# 0009_e_field_probe_5mm.net
KiCad netlist of a schematic drawn in EAGLE
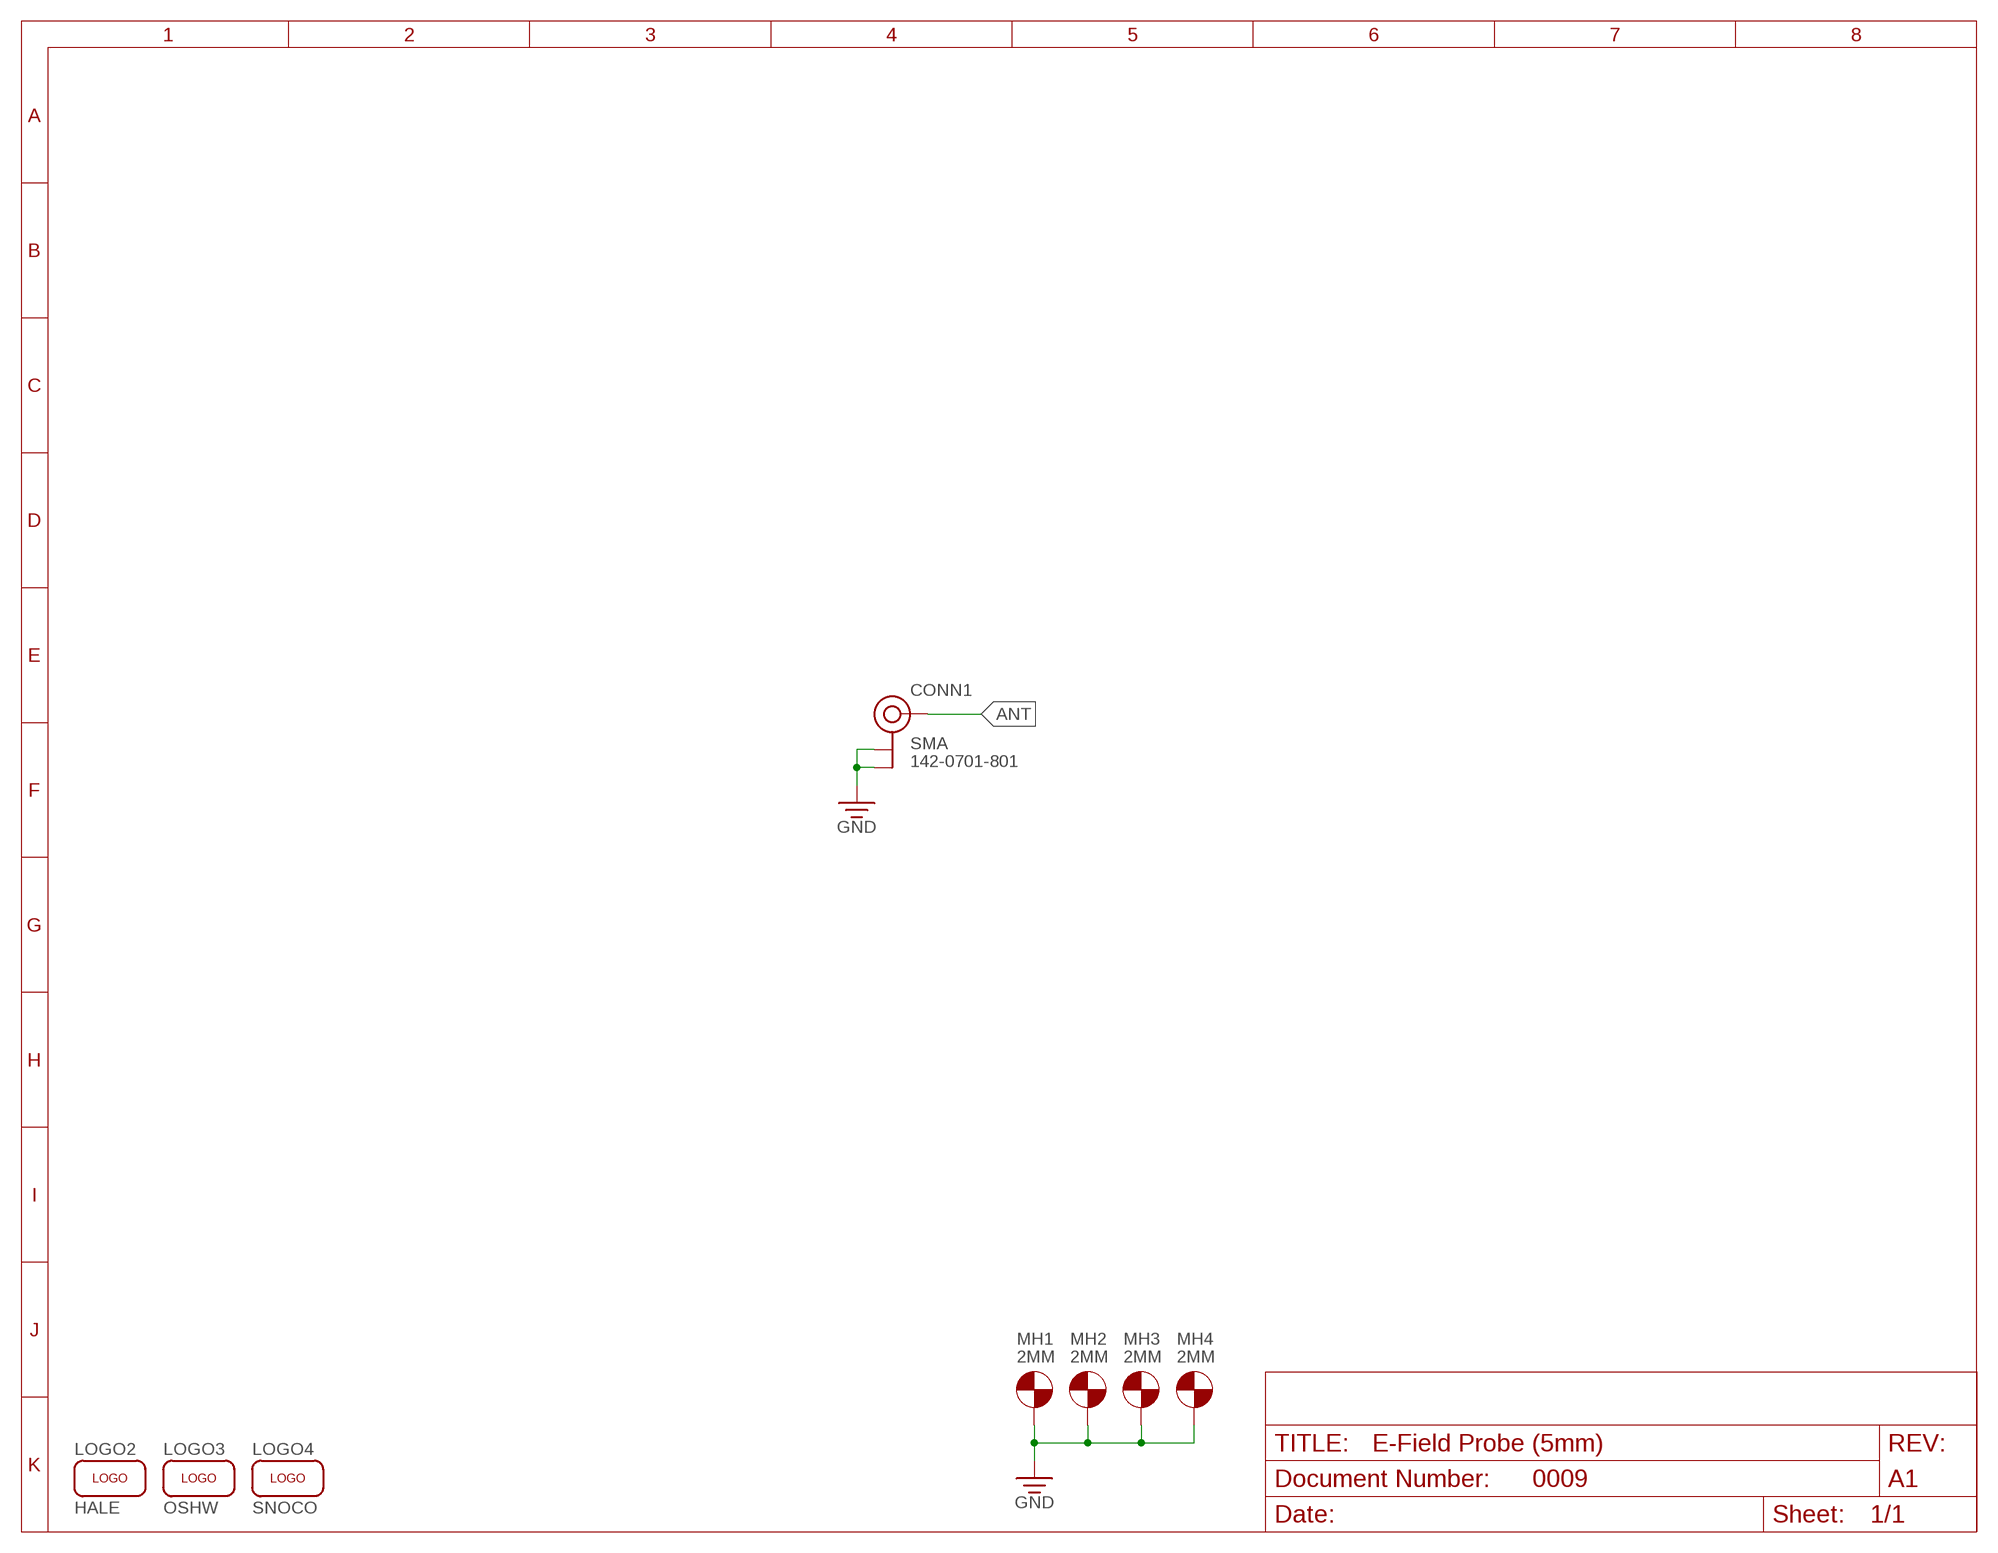
[diagram p0: schematic, sheet 1]

(export (version "E")
  (design (tool "Eeschema 10.0.6"))
  (components
    (comp (ref "CONN1")
      (value "SMA")
      (footprint "eagle-import:SMA-142-0701-801")
      (fields (field (name "MFG") "Cinch Connectivity Solutions Johnson"))
      (libsource (lib "eagle-import") (part "COAX-CONNECTOR-EDGE-SMA"))
    )
    (comp (ref "LOGO2")
      (value "HALE")
      (footprint "eagle-import:HALE-SILK-ICON")
      (libsource (lib "eagle-import") (part "LOGO-HALE"))
    )
    (comp (ref "LOGO3")
      (value "OSHW")
      (footprint "eagle-import:OSHW-SILK-ICON")
      (libsource (lib "eagle-import") (part "LOGO-OSHW"))
    )
    (comp (ref "LOGO4")
      (value "SNOCO")
      (footprint "eagle-import:SNOCO-SILK-ICON")
      (libsource (lib "eagle-import") (part "LOGO-SNOCO"))
    )
    (comp (ref "MH1")
      (value "2MM")
      (footprint "eagle-import:MH-M2-ELEC")
      (libsource (lib "eagle-import") (part "MH-ELEC-M2"))
    )
    (comp (ref "MH2")
      (value "2MM")
      (footprint "eagle-import:MH-M2-ELEC")
      (libsource (lib "eagle-import") (part "MH-ELEC-M2"))
    )
    (comp (ref "MH3")
      (value "2MM")
      (footprint "eagle-import:MH-M2-ELEC")
      (libsource (lib "eagle-import") (part "MH-ELEC-M2"))
    )
    (comp (ref "MH4")
      (value "2MM")
      (footprint "eagle-import:MH-M2-ELEC")
      (libsource (lib "eagle-import") (part "MH-ELEC-M2"))
    )
    (comp (ref "U$2")
      (value "FRAME-8.5X11-LANDSCAPE-LET")
      (footprint "eagle-import:FRAME-8.5X11-LANDSCAPE")
      (fields (field (name "DOCNUM") "0009") (field (name "TITLE") "E-Field Probe (5mm)"))
      (libsource (lib "eagle-import") (part "FRAME-8.5X11-LANDSCAPE-LET"))
    )
  )
  (nets
    (net (code "1") (name "ANT") (class "Default")
      (node (ref "CONN1") (pin "2") (pinfunction "SIGNAL_2") (pintype "passive"))
    )
    (net (code "2") (name "GND") (class "Default")
      (node (ref "CONN1") (pin "1") (pinfunction "GND_1") (pintype "power_in"))
      (node (ref "CONN1") (pin "3") (pinfunction "GND_3") (pintype "power_in"))
      (node (ref "CONN1") (pin "4") (pinfunction "GND_4") (pintype "power_in"))
      (node (ref "CONN1") (pin "5") (pinfunction "GND_5") (pintype "power_in"))
      (node (ref "MH1") (pin "1") (pinfunction "1_1") (pintype "passive"))
      (node (ref "MH2") (pin "1") (pinfunction "1_1") (pintype "passive"))
      (node (ref "MH3") (pin "1") (pinfunction "1_1") (pintype "passive"))
      (node (ref "MH4") (pin "1") (pinfunction "1_1") (pintype "passive"))
    )
  )
)
